# CPU.net
KiCad netlist of a schematic drawn in Altium Designer
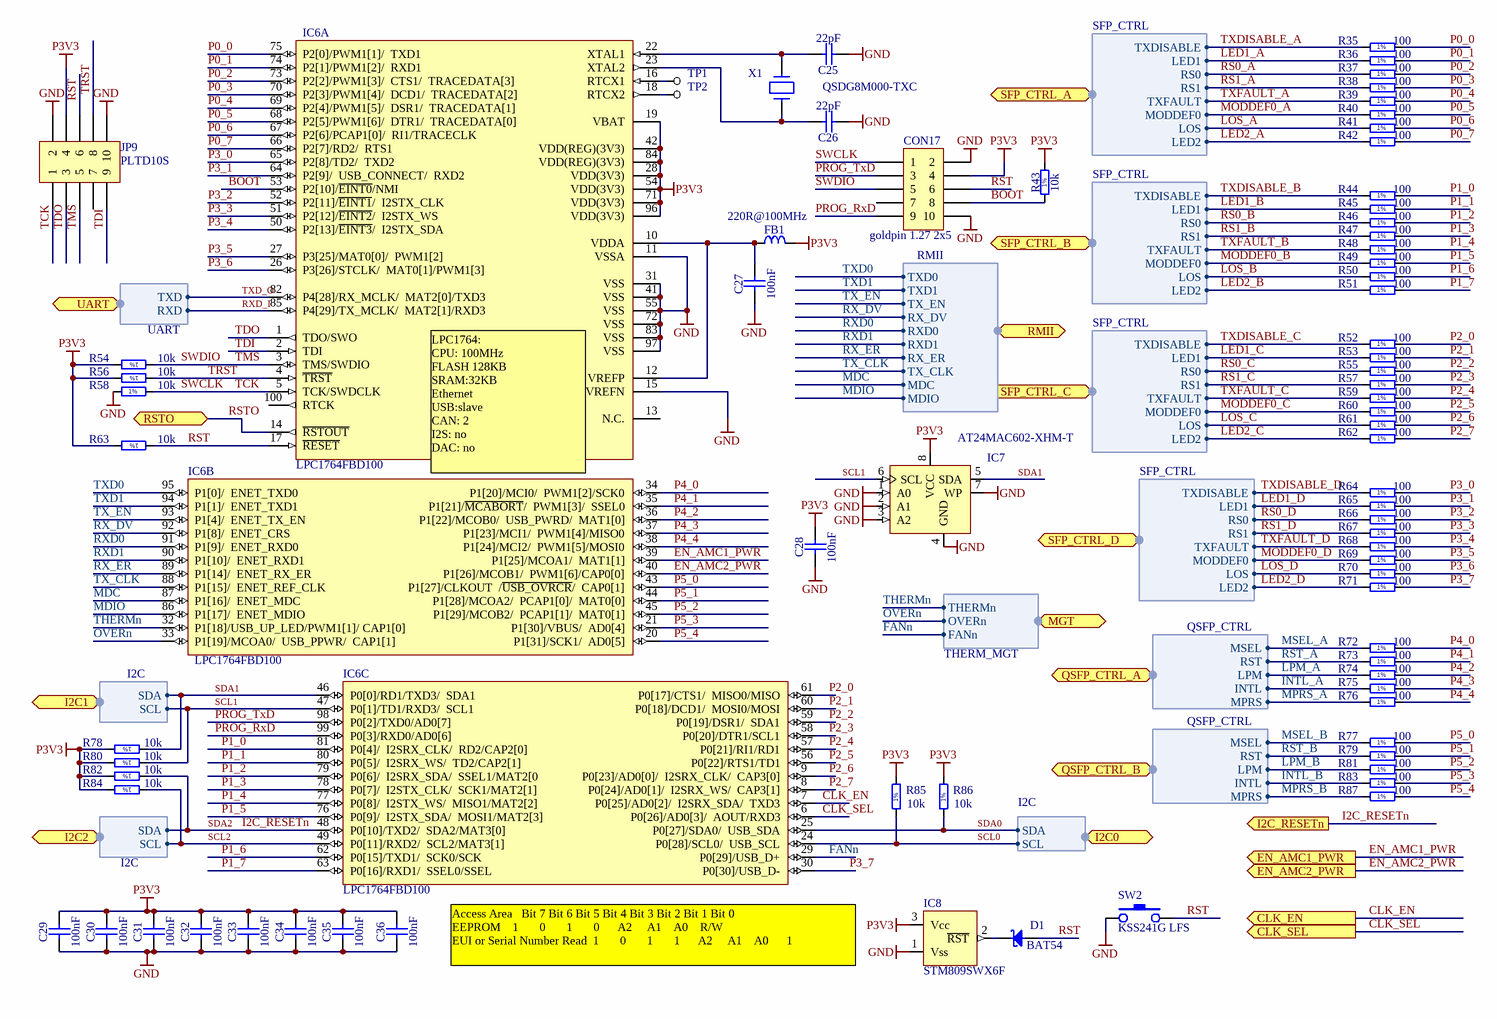
[diagram p0: CPU.SchDoc]

(export (version "E")
  (design (tool "Eeschema 10.0.6"))
  (components
    (comp (ref "C25")
      (value "22pF")
      (footprint "CAPC1005X55N")
      (description "Non-polarised capacitor")
      (fields
        (field (name "PART NUMBER") "CC0402_22PF_50V_5%_NP0")
        (field (name "VOLTAGE") "50V")
        (field (name "AUTHOR") "CERN DEM JLC")
      )
      (libsource (lib "Capacitors") (part "Capacitor - non polarized"))
    )
    (comp (ref "C26")
      (value "22pF")
      (footprint "CAPC1005X55N")
      (description "Non-polarised capacitor")
      (fields
        (field (name "PART NUMBER") "CC0402_22PF_50V_5%_NP0")
        (field (name "VOLTAGE") "50V")
        (field (name "AUTHOR") "CERN DEM JLC")
      )
      (libsource (lib "Capacitors") (part "Capacitor - non polarized"))
    )
    (comp (ref "C27")
      (value "100nF")
      (footprint "CAPC0603X33N")
      (description "Non-polarised capacitor")
      (fields
        (field (name "PART NUMBER") "CC0201_100NF_6.3V_10%_X5R")
        (field (name "VOLTAGE") "6.3V")
        (field (name "AUTHOR") "CERN DEM JLC")
      )
      (libsource (lib "Capacitors") (part "Capacitor - non polarized"))
    )
    (comp (ref "C28")
      (value "100nF")
      (footprint "CAPC0603X33N")
      (description "Non-polarised capacitor")
      (fields
        (field (name "PART NUMBER") "CC0201_100NF_6.3V_10%_X5R")
        (field (name "VOLTAGE") "6.3V")
        (field (name "AUTHOR") "CERN DEM JLC")
      )
      (libsource (lib "Capacitors") (part "Capacitor - non polarized"))
    )
    (comp (ref "C29")
      (value "100nF")
      (footprint "CAPC0603X33N")
      (description "Non-polarised capacitor")
      (fields
        (field (name "PART NUMBER") "CC0201_100NF_6.3V_10%_X5R")
        (field (name "VOLTAGE") "6.3V")
        (field (name "AUTHOR") "CERN DEM JLC")
      )
      (libsource (lib "Capacitors") (part "Capacitor - non polarized"))
    )
    (comp (ref "C30")
      (value "100nF")
      (footprint "CAPC0603X33N")
      (description "Non-polarised capacitor")
      (fields
        (field (name "PART NUMBER") "CC0201_100NF_6.3V_10%_X5R")
        (field (name "VOLTAGE") "6.3V")
        (field (name "AUTHOR") "CERN DEM JLC")
      )
      (libsource (lib "Capacitors") (part "Capacitor - non polarized"))
    )
    (comp (ref "C31")
      (value "100nF")
      (footprint "CAPC0603X33N")
      (description "Non-polarised capacitor")
      (fields
        (field (name "PART NUMBER") "CC0201_100NF_6.3V_10%_X5R")
        (field (name "VOLTAGE") "6.3V")
        (field (name "AUTHOR") "CERN DEM JLC")
      )
      (libsource (lib "Capacitors") (part "Capacitor - non polarized"))
    )
    (comp (ref "C32")
      (value "100nF")
      (footprint "CAPC0603X33N")
      (description "Non-polarised capacitor")
      (fields
        (field (name "PART NUMBER") "CC0201_100NF_6.3V_10%_X5R")
        (field (name "VOLTAGE") "6.3V")
        (field (name "AUTHOR") "CERN DEM JLC")
      )
      (libsource (lib "Capacitors") (part "Capacitor - non polarized"))
    )
    (comp (ref "C33")
      (value "100nF")
      (footprint "CAPC0603X33N")
      (description "Non-polarised capacitor")
      (fields
        (field (name "PART NUMBER") "CC0201_100NF_6.3V_10%_X5R")
        (field (name "VOLTAGE") "6.3V")
        (field (name "AUTHOR") "CERN DEM JLC")
      )
      (libsource (lib "Capacitors") (part "Capacitor - non polarized"))
    )
    (comp (ref "C34")
      (value "100nF")
      (footprint "CAPC0603X33N")
      (description "Non-polarised capacitor")
      (fields
        (field (name "PART NUMBER") "CC0201_100NF_6.3V_10%_X5R")
        (field (name "VOLTAGE") "6.3V")
        (field (name "AUTHOR") "CERN DEM JLC")
      )
      (libsource (lib "Capacitors") (part "Capacitor - non polarized"))
    )
    (comp (ref "C35")
      (value "100nF")
      (footprint "CAPC0603X33N")
      (description "Non-polarised capacitor")
      (fields
        (field (name "PART NUMBER") "CC0201_100NF_6.3V_10%_X5R")
        (field (name "VOLTAGE") "6.3V")
        (field (name "AUTHOR") "CERN DEM JLC")
      )
      (libsource (lib "Capacitors") (part "Capacitor - non polarized"))
    )
    (comp (ref "C36")
      (value "100nF")
      (footprint "CAPC0603X33N")
      (description "Non-polarised capacitor")
      (fields
        (field (name "PART NUMBER") "CC0201_100NF_6.3V_10%_X5R")
        (field (name "VOLTAGE") "6.3V")
        (field (name "AUTHOR") "CERN DEM JLC")
      )
      (libsource (lib "Capacitors") (part "Capacitor - non polarized"))
    )
    (comp (ref "CON17")
      (value "goldpin 1.27 2x5")
      (footprint "CON_2x5_MINI")
      (description "PBTD10S")
      (libsource (lib "sch") (part "CON_HEADER 5X2"))
    )
    (comp (ref "D1")
      (value "BAT54")
      (footprint "SOT95P240X130-3N")
      (description "Diode Schottky  Anode Pin 1 Cathode Pin 3 (Pas de pin 2)")
      (fields
        (field (name "VOLTAGE") "30V")
        (field (name "POWER") "200mA")
        (field (name "AUTHOR") "CERN DEM JLC")
      )
      (libsource (lib "ICs And Semiconductors") (part "Diode Schottky A1C3"))
    )
    (comp (ref "FB1")
      (value "220R@100MHz")
      (footprint "INDC2012X105N")
      (description "Inductor")
      (fields
        (field (name "PART NUMBER") "IND0805_MURATA_BLM21PG221SN1D")
        (field (name "POWER") "2A")
        (field (name "AUTHOR") "CERN DEM JLC")
      )
      (libsource (lib "Inductors & Transformers") (part "Inductor"))
    )
    (comp (ref "IC6")
      (value "LPC1764FBD100")
      (footprint "LQFP100-LPC")
      (description "ARM Cortex-M3 procesor")
      (libsource (lib "LIBRARY_SCH") (part "UPC_LPC1764"))
    )
    (comp (ref "IC7")
      (value "AT24MAC602-XHM-T")
      (footprint "TSSOP-8")
      (description "Serial 2K EEPROM+ 48bit MAC")
      (libsource (lib "LIBRARY_SCH") (part "MEM_24MAC602"))
    )
    (comp (ref "IC8")
      (value "STM809SWX6F")
      (footprint "SOT-23")
      (description "2.93V  Reset circuit")
      (libsource (lib "LIBRARY_SCH") (part "VMON_STM809"))
    )
    (comp (ref "JP9")
      (value "PLTD10S")
      (footprint "PLTD10S")
      (description "Goldpin 2.54mm, male header")
      (libsource (lib "LIBRARY_SCH") (part "CON_2x5 2.54 male SMT"))
    )
    (comp (ref "R35")
      (value "100")
      (footprint "RESC1005X40N")
      (description "Resistor - 1%")
      (fields
        (field (name "PART NUMBER") "R0402_100R_1%_0.0625W_100PPM")
        (field (name "POWER") "0.0625W")
        (field (name "AUTHOR") "CERN DEM JLC")
      )
      (libsource (lib "Resistors") (part "Resistor - 1%"))
    )
    (comp (ref "R36")
      (value "100")
      (footprint "RESC1005X40N")
      (description "Resistor - 1%")
      (fields
        (field (name "PART NUMBER") "R0402_100R_1%_0.0625W_100PPM")
        (field (name "POWER") "0.0625W")
        (field (name "AUTHOR") "CERN DEM JLC")
      )
      (libsource (lib "Resistors") (part "Resistor - 1%"))
    )
    (comp (ref "R37")
      (value "100")
      (footprint "RESC1005X40N")
      (description "Resistor - 1%")
      (fields
        (field (name "PART NUMBER") "R0402_100R_1%_0.0625W_100PPM")
        (field (name "POWER") "0.0625W")
        (field (name "AUTHOR") "CERN DEM JLC")
      )
      (libsource (lib "Resistors") (part "Resistor - 1%"))
    )
    (comp (ref "R38")
      (value "100")
      (footprint "RESC1005X40N")
      (description "Resistor - 1%")
      (fields
        (field (name "PART NUMBER") "R0402_100R_1%_0.0625W_100PPM")
        (field (name "POWER") "0.0625W")
        (field (name "AUTHOR") "CERN DEM JLC")
      )
      (libsource (lib "Resistors") (part "Resistor - 1%"))
    )
    (comp (ref "R39")
      (value "100")
      (footprint "RESC1005X40N")
      (description "Resistor - 1%")
      (fields
        (field (name "PART NUMBER") "R0402_100R_1%_0.0625W_100PPM")
        (field (name "POWER") "0.0625W")
        (field (name "AUTHOR") "CERN DEM JLC")
      )
      (libsource (lib "Resistors") (part "Resistor - 1%"))
    )
    (comp (ref "R40")
      (value "100")
      (footprint "RESC1005X40N")
      (description "Resistor - 1%")
      (fields
        (field (name "PART NUMBER") "R0402_100R_1%_0.0625W_100PPM")
        (field (name "POWER") "0.0625W")
        (field (name "AUTHOR") "CERN DEM JLC")
      )
      (libsource (lib "Resistors") (part "Resistor - 1%"))
    )
    (comp (ref "R41")
      (value "100")
      (footprint "RESC1005X40N")
      (description "Resistor - 1%")
      (fields
        (field (name "PART NUMBER") "R0402_100R_1%_0.0625W_100PPM")
        (field (name "POWER") "0.0625W")
        (field (name "AUTHOR") "CERN DEM JLC")
      )
      (libsource (lib "Resistors") (part "Resistor - 1%"))
    )
    (comp (ref "R42")
      (value "100")
      (footprint "RESC1005X40N")
      (description "Resistor - 1%")
      (fields
        (field (name "PART NUMBER") "R0402_100R_1%_0.0625W_100PPM")
        (field (name "POWER") "0.0625W")
        (field (name "AUTHOR") "CERN DEM JLC")
      )
      (libsource (lib "Resistors") (part "Resistor - 1%"))
    )
    (comp (ref "R43")
      (value "10k")
      (footprint "RESC1005X40N")
      (description "Resistor - 1%")
      (fields
        (field (name "PART NUMBER") "R0402_10K_1%_0.0625W_100PPM")
        (field (name "POWER") "0.0625W")
        (field (name "AUTHOR") "CERN DEM JLC")
      )
      (libsource (lib "Resistors") (part "Resistor - 1%"))
    )
    (comp (ref "R44")
      (value "100")
      (footprint "RESC1005X40N")
      (description "Resistor - 1%")
      (fields
        (field (name "PART NUMBER") "R0402_100R_1%_0.0625W_100PPM")
        (field (name "POWER") "0.0625W")
        (field (name "AUTHOR") "CERN DEM JLC")
      )
      (libsource (lib "Resistors") (part "Resistor - 1%"))
    )
    (comp (ref "R45")
      (value "100")
      (footprint "RESC1005X40N")
      (description "Resistor - 1%")
      (fields
        (field (name "PART NUMBER") "R0402_100R_1%_0.0625W_100PPM")
        (field (name "POWER") "0.0625W")
        (field (name "AUTHOR") "CERN DEM JLC")
      )
      (libsource (lib "Resistors") (part "Resistor - 1%"))
    )
    (comp (ref "R46")
      (value "100")
      (footprint "RESC1005X40N")
      (description "Resistor - 1%")
      (fields
        (field (name "PART NUMBER") "R0402_100R_1%_0.0625W_100PPM")
        (field (name "POWER") "0.0625W")
        (field (name "AUTHOR") "CERN DEM JLC")
      )
      (libsource (lib "Resistors") (part "Resistor - 1%"))
    )
    (comp (ref "R47")
      (value "100")
      (footprint "RESC1005X40N")
      (description "Resistor - 1%")
      (fields
        (field (name "PART NUMBER") "R0402_100R_1%_0.0625W_100PPM")
        (field (name "POWER") "0.0625W")
        (field (name "AUTHOR") "CERN DEM JLC")
      )
      (libsource (lib "Resistors") (part "Resistor - 1%"))
    )
    (comp (ref "R48")
      (value "100")
      (footprint "RESC1005X40N")
      (description "Resistor - 1%")
      (fields
        (field (name "PART NUMBER") "R0402_100R_1%_0.0625W_100PPM")
        (field (name "POWER") "0.0625W")
        (field (name "AUTHOR") "CERN DEM JLC")
      )
      (libsource (lib "Resistors") (part "Resistor - 1%"))
    )
    (comp (ref "R49")
      (value "100")
      (footprint "RESC1005X40N")
      (description "Resistor - 1%")
      (fields
        (field (name "PART NUMBER") "R0402_100R_1%_0.0625W_100PPM")
        (field (name "POWER") "0.0625W")
        (field (name "AUTHOR") "CERN DEM JLC")
      )
      (libsource (lib "Resistors") (part "Resistor - 1%"))
    )
    (comp (ref "R50")
      (value "100")
      (footprint "RESC1005X40N")
      (description "Resistor - 1%")
      (fields
        (field (name "PART NUMBER") "R0402_100R_1%_0.0625W_100PPM")
        (field (name "POWER") "0.0625W")
        (field (name "AUTHOR") "CERN DEM JLC")
      )
      (libsource (lib "Resistors") (part "Resistor - 1%"))
    )
    (comp (ref "R51")
      (value "100")
      (footprint "RESC1005X40N")
      (description "Resistor - 1%")
      (fields
        (field (name "PART NUMBER") "R0402_100R_1%_0.0625W_100PPM")
        (field (name "POWER") "0.0625W")
        (field (name "AUTHOR") "CERN DEM JLC")
      )
      (libsource (lib "Resistors") (part "Resistor - 1%"))
    )
    (comp (ref "R52")
      (value "100")
      (footprint "RESC1005X40N")
      (description "Resistor - 1%")
      (fields
        (field (name "PART NUMBER") "R0402_100R_1%_0.0625W_100PPM")
        (field (name "POWER") "0.0625W")
        (field (name "AUTHOR") "CERN DEM JLC")
      )
      (libsource (lib "Resistors") (part "Resistor - 1%"))
    )
    (comp (ref "R53")
      (value "100")
      (footprint "RESC1005X40N")
      (description "Resistor - 1%")
      (fields
        (field (name "PART NUMBER") "R0402_100R_1%_0.0625W_100PPM")
        (field (name "POWER") "0.0625W")
        (field (name "AUTHOR") "CERN DEM JLC")
      )
      (libsource (lib "Resistors") (part "Resistor - 1%"))
    )
    (comp (ref "R54")
      (value "10k")
      (footprint "RESC1005X40N")
      (description "Resistor - 1%")
      (fields
        (field (name "PART NUMBER") "R0402_10K_1%_0.0625W_100PPM")
        (field (name "POWER") "0.0625W")
        (field (name "AUTHOR") "CERN DEM JLC")
      )
      (libsource (lib "Resistors") (part "Resistor - 1%"))
    )
    (comp (ref "R55")
      (value "100")
      (footprint "RESC1005X40N")
      (description "Resistor - 1%")
      (fields
        (field (name "PART NUMBER") "R0402_100R_1%_0.0625W_100PPM")
        (field (name "POWER") "0.0625W")
        (field (name "AUTHOR") "CERN DEM JLC")
      )
      (libsource (lib "Resistors") (part "Resistor - 1%"))
    )
    (comp (ref "R56")
      (value "10k")
      (footprint "RESC1005X40N")
      (description "Resistor - 1%")
      (fields
        (field (name "PART NUMBER") "R0402_10K_1%_0.0625W_100PPM")
        (field (name "POWER") "0.0625W")
        (field (name "AUTHOR") "CERN DEM JLC")
      )
      (libsource (lib "Resistors") (part "Resistor - 1%"))
    )
    (comp (ref "R57")
      (value "100")
      (footprint "RESC1005X40N")
      (description "Resistor - 1%")
      (fields
        (field (name "PART NUMBER") "R0402_100R_1%_0.0625W_100PPM")
        (field (name "POWER") "0.0625W")
        (field (name "AUTHOR") "CERN DEM JLC")
      )
      (libsource (lib "Resistors") (part "Resistor - 1%"))
    )
    (comp (ref "R58")
      (value "10k")
      (footprint "RESC1005X40N")
      (description "Resistor - 1%")
      (fields
        (field (name "PART NUMBER") "R0402_10K_1%_0.0625W_100PPM")
        (field (name "POWER") "0.0625W")
        (field (name "AUTHOR") "CERN DEM JLC")
      )
      (libsource (lib "Resistors") (part "Resistor - 1%"))
    )
    (comp (ref "R59")
      (value "100")
      (footprint "RESC1005X40N")
      (description "Resistor - 1%")
      (fields
        (field (name "PART NUMBER") "R0402_100R_1%_0.0625W_100PPM")
        (field (name "POWER") "0.0625W")
        (field (name "AUTHOR") "CERN DEM JLC")
      )
      (libsource (lib "Resistors") (part "Resistor - 1%"))
    )
    (comp (ref "R60")
      (value "100")
      (footprint "RESC1005X40N")
      (description "Resistor - 1%")
      (fields
        (field (name "PART NUMBER") "R0402_100R_1%_0.0625W_100PPM")
        (field (name "POWER") "0.0625W")
        (field (name "AUTHOR") "CERN DEM JLC")
      )
      (libsource (lib "Resistors") (part "Resistor - 1%"))
    )
    (comp (ref "R61")
      (value "100")
      (footprint "RESC1005X40N")
      (description "Resistor - 1%")
      (fields
        (field (name "PART NUMBER") "R0402_100R_1%_0.0625W_100PPM")
        (field (name "POWER") "0.0625W")
        (field (name "AUTHOR") "CERN DEM JLC")
      )
      (libsource (lib "Resistors") (part "Resistor - 1%"))
    )
    (comp (ref "R62")
      (value "100")
      (footprint "RESC1005X40N")
      (description "Resistor - 1%")
      (fields
        (field (name "PART NUMBER") "R0402_100R_1%_0.0625W_100PPM")
        (field (name "POWER") "0.0625W")
        (field (name "AUTHOR") "CERN DEM JLC")
      )
      (libsource (lib "Resistors") (part "Resistor - 1%"))
    )
    (comp (ref "R63")
      (value "10k")
      (footprint "RESC1005X40N")
      (description "Resistor - 1%")
      (fields
        (field (name "PART NUMBER") "R0402_10K_1%_0.0625W_100PPM")
        (field (name "POWER") "0.0625W")
        (field (name "AUTHOR") "CERN DEM JLC")
      )
      (libsource (lib "Resistors") (part "Resistor - 1%"))
    )
    (comp (ref "R64")
      (value "100")
      (footprint "RESC1005X40N")
      (description "Resistor - 1%")
      (fields
        (field (name "PART NUMBER") "R0402_100R_1%_0.0625W_100PPM")
        (field (name "POWER") "0.0625W")
        (field (name "AUTHOR") "CERN DEM JLC")
      )
      (libsource (lib "Resistors") (part "Resistor - 1%"))
    )
    (comp (ref "R65")
      (value "100")
      (footprint "RESC1005X40N")
      (description "Resistor - 1%")
      (fields
        (field (name "PART NUMBER") "R0402_100R_1%_0.0625W_100PPM")
        (field (name "POWER") "0.0625W")
        (field (name "AUTHOR") "CERN DEM JLC")
      )
      (libsource (lib "Resistors") (part "Resistor - 1%"))
    )
    (comp (ref "R66")
      (value "100")
      (footprint "RESC1005X40N")
      (description "Resistor - 1%")
      (fields
        (field (name "PART NUMBER") "R0402_100R_1%_0.0625W_100PPM")
        (field (name "POWER") "0.0625W")
        (field (name "AUTHOR") "CERN DEM JLC")
      )
      (libsource (lib "Resistors") (part "Resistor - 1%"))
    )
    (comp (ref "R67")
      (value "100")
      (footprint "RESC1005X40N")
      (description "Resistor - 1%")
      (fields
        (field (name "PART NUMBER") "R0402_100R_1%_0.0625W_100PPM")
        (field (name "POWER") "0.0625W")
        (field (name "AUTHOR") "CERN DEM JLC")
      )
      (libsource (lib "Resistors") (part "Resistor - 1%"))
    )
    (comp (ref "R68")
      (value "100")
      (footprint "RESC1005X40N")
      (description "Resistor - 1%")
      (fields
        (field (name "PART NUMBER") "R0402_100R_1%_0.0625W_100PPM")
        (field (name "POWER") "0.0625W")
        (field (name "AUTHOR") "CERN DEM JLC")
      )
      (libsource (lib "Resistors") (part "Resistor - 1%"))
    )
    (comp (ref "R69")
      (value "100")
      (footprint "RESC1005X40N")
      (description "Resistor - 1%")
      (fields
        (field (name "PART NUMBER") "R0402_100R_1%_0.0625W_100PPM")
        (field (name "POWER") "0.0625W")
        (field (name "AUTHOR") "CERN DEM JLC")
      )
      (libsource (lib "Resistors") (part "Resistor - 1%"))
    )
    (comp (ref "R70")
      (value "100")
      (footprint "RESC1005X40N")
      (description "Resistor - 1%")
      (fields
        (field (name "PART NUMBER") "R0402_100R_1%_0.0625W_100PPM")
        (field (name "POWER") "0.0625W")
        (field (name "AUTHOR") "CERN DEM JLC")
      )
      (libsource (lib "Resistors") (part "Resistor - 1%"))
    )
    (comp (ref "R71")
      (value "100")
      (footprint "RESC1005X40N")
      (description "Resistor - 1%")
      (fields
        (field (name "PART NUMBER") "R0402_100R_1%_0.0625W_100PPM")
        (field (name "POWER") "0.0625W")
        (field (name "AUTHOR") "CERN DEM JLC")
      )
      (libsource (lib "Resistors") (part "Resistor - 1%"))
    )
    (comp (ref "R72")
      (value "100")
      (footprint "RESC1005X40N")
      (description "Resistor - 1%")
      (fields
        (field (name "PART NUMBER") "R0402_100R_1%_0.0625W_100PPM")
        (field (name "POWER") "0.0625W")
        (field (name "AUTHOR") "CERN DEM JLC")
      )
      (libsource (lib "Resistors") (part "Resistor - 1%"))
    )
    (comp (ref "R73")
      (value "100")
      (footprint "RESC1005X40N")
      (description "Resistor - 1%")
      (fields
        (field (name "PART NUMBER") "R0402_100R_1%_0.0625W_100PPM")
        (field (name "POWER") "0.0625W")
        (field (name "AUTHOR") "CERN DEM JLC")
      )
      (libsource (lib "Resistors") (part "Resistor - 1%"))
    )
    (comp (ref "R74")
      (value "100")
      (footprint "RESC1005X40N")
      (description "Resistor - 1%")
      (fields
        (field (name "PART NUMBER") "R0402_100R_1%_0.0625W_100PPM")
        (field (name "POWER") "0.0625W")
        (field (name "AUTHOR") "CERN DEM JLC")
      )
      (libsource (lib "Resistors") (part "Resistor - 1%"))
    )
    (comp (ref "R75")
      (value "100")
      (footprint "RESC1005X40N")
      (description "Resistor - 1%")
      (fields
        (field (name "PART NUMBER") "R0402_100R_1%_0.0625W_100PPM")
        (field (name "POWER") "0.0625W")
        (field (name "AUTHOR") "CERN DEM JLC")
      )
      (libsource (lib "Resistors") (part "Resistor - 1%"))
    )
    (comp (ref "R76")
      (value "100")
      (footprint "RESC1005X40N")
      (description "Resistor - 1%")
      (fields
        (field (name "PART NUMBER") "R0402_100R_1%_0.0625W_100PPM")
        (field (name "POWER") "0.0625W")
        (field (name "AUTHOR") "CERN DEM JLC")
      )
      (libsource (lib "Resistors") (part "Resistor - 1%"))
    )
    (comp (ref "R77")
      (value "100")
      (footprint "RESC1005X40N")
      (description "Resistor - 1%")
      (fields
        (field (name "PART NUMBER") "R0402_100R_1%_0.0625W_100PPM")
        (field (name "POWER") "0.0625W")
        (field (name "AUTHOR") "CERN DEM JLC")
      )
      (libsource (lib "Resistors") (part "Resistor - 1%"))
    )
    (comp (ref "R78")
      (value "10k")
      (footprint "RESC1005X40N")
      (description "Resistor - 1%")
      (fields
        (field (name "PART NUMBER") "R0402_10K_1%_0.0625W_100PPM")
        (field (name "POWER") "0.0625W")
        (field (name "AUTHOR") "CERN DEM JLC")
      )
      (libsource (lib "Resistors") (part "Resistor - 1%"))
    )
    (comp (ref "R79")
      (value "100")
      (footprint "RESC1005X40N")
      (description "Resistor - 1%")
      (fields
        (field (name "PART NUMBER") "R0402_100R_1%_0.0625W_100PPM")
        (field (name "POWER") "0.0625W")
        (field (name "AUTHOR") "CERN DEM JLC")
      )
      (libsource (lib "Resistors") (part "Resistor - 1%"))
    )
    (comp (ref "R80")
      (value "10k")
      (footprint "RESC1005X40N")
      (description "Resistor - 1%")
      (fields
        (field (name "PART NUMBER") "R0402_10K_1%_0.0625W_100PPM")
        (field (name "POWER") "0.0625W")
        (field (name "AUTHOR") "CERN DEM JLC")
      )
      (libsource (lib "Resistors") (part "Resistor - 1%"))
    )
    (comp (ref "R81")
      (value "100")
      (footprint "RESC1005X40N")
      (description "Resistor - 1%")
      (fields
        (field (name "PART NUMBER") "R0402_100R_1%_0.0625W_100PPM")
        (field (name "POWER") "0.0625W")
        (field (name "AUTHOR") "CERN DEM JLC")
      )
      (libsource (lib "Resistors") (part "Resistor - 1%"))
    )
    (comp (ref "R82")
      (value "10k")
      (footprint "RESC1005X40N")
      (description "Resistor - 1%")
      (fields
        (field (name "PART NUMBER") "R0402_10K_1%_0.0625W_100PPM")
        (field (name "POWER") "0.0625W")
        (field (name "AUTHOR") "CERN DEM JLC")
      )
      (libsource (lib "Resistors") (part "Resistor - 1%"))
    )
    (comp (ref "R83")
      (value "100")
      (footprint "RESC1005X40N")
      (description "Resistor - 1%")
      (fields
        (field (name "PART NUMBER") "R0402_100R_1%_0.0625W_100PPM")
        (field (name "POWER") "0.0625W")
        (field (name "AUTHOR") "CERN DEM JLC")
      )
      (libsource (lib "Resistors") (part "Resistor - 1%"))
    )
    (comp (ref "R84")
      (value "10k")
      (footprint "RESC1005X40N")
      (description "Resistor - 1%")
      (fields
        (field (name "PART NUMBER") "R0402_10K_1%_0.0625W_100PPM")
        (field (name "POWER") "0.0625W")
        (field (name "AUTHOR") "CERN DEM JLC")
      )
      (libsource (lib "Resistors") (part "Resistor - 1%"))
    )
    (comp (ref "R85")
      (value "10k")
      (footprint "RESC1005X40N")
      (description "Resistor - 1%")
      (fields
        (field (name "PART NUMBER") "R0402_10K_1%_0.0625W_100PPM")
        (field (name "POWER") "0.0625W")
        (field (name "AUTHOR") "CERN DEM JLC")
      )
      (libsource (lib "Resistors") (part "Resistor - 1%"))
    )
    (comp (ref "R86")
      (value "10k")
      (footprint "RESC1005X40N")
      (description "Resistor - 1%")
      (fields
        (field (name "PART NUMBER") "R0402_10K_1%_0.0625W_100PPM")
        (field (name "POWER") "0.0625W")
        (field (name "AUTHOR") "CERN DEM JLC")
      )
      (libsource (lib "Resistors") (part "Resistor - 1%"))
    )
    (comp (ref "R87")
      (value "100")
      (footprint "RESC1005X40N")
      (description "Resistor - 1%")
      (fields
        (field (name "PART NUMBER") "R0402_100R_1%_0.0625W_100PPM")
        (field (name "POWER") "0.0625W")
        (field (name "AUTHOR") "CERN DEM JLC")
      )
      (libsource (lib "Resistors") (part "Resistor - 1%"))
    )
    (comp (ref "SW2")
      (value "KSS241G LFS")
      (footprint "KSS241G LFS")
      (description "Push button")
      (libsource (lib "LIBRARY_SCH") (part "SW-TACT_SMD_RA_mini"))
    )
    (comp (ref "TP1")
      (value "TP")
      (footprint "TP")
      (description "Testpoint")
      (libsource (lib "LIBRARY_SCH") (part "TP"))
    )
    (comp (ref "TP2")
      (value "TP")
      (footprint "TP")
      (description "Testpoint")
      (libsource (lib "LIBRARY_SCH") (part "TP"))
    )
    (comp (ref "X1")
      (value "QSDG8M000-TXC")
      (footprint "XTAL_5.0*3.2")
      (description "miniature crystal oscillator (Maritex) QSDG8M000-TXC")
      (libsource (lib "LIBRARY_SCH") (part "X_CRYSTAL_SMD_5.0*3.2"))
    )
  )
  (nets
    (net (code "7") (name "/BOOT") (class "Default")
      (node (ref "CON17") (pin "8") (pinfunction "8_8") (pintype "passive"))
      (node (ref "IC6") (pin "53") (pinfunction "P2[10]/~{EINT0}/NMI_53") (pintype "bidirectional"))
      (node (ref "R43") (pin "1") (pinfunction "1_1") (pintype "passive"))
    )
    (net (code "8") (name "/CLK_EN") (class "Default")
      (node (ref "IC6") (pin "7") (pinfunction "P0[25]/AD0[2]/__I2SRX_SDA/__TXD3_7") (pintype "bidirectional"))
    )
    (net (code "9") (name "/CLK_SEL") (class "Default")
      (node (ref "IC6") (pin "6") (pinfunction "P0[26]/AD0[3]/__AOUT/RXD3_6") (pintype "bidirectional"))
    )
    (net (code "10") (name "/EN_AMC1_PWR") (class "Default")
      (node (ref "IC6") (pin "39") (pinfunction "P1[25]/MCOA1/__MAT1[1]_39") (pintype "bidirectional"))
    )
    (net (code "11") (name "/EN_AMC2_PWR") (class "Default")
      (node (ref "IC6") (pin "40") (pinfunction "P1[26]/MCOB1/__PWM1[6]/CAP0[0]_40") (pintype "bidirectional"))
    )
    (net (code "12") (name "/FANn") (class "Default")
      (node (ref "IC6") (pin "29") (pinfunction "P0[29]/USB_D+_29") (pintype "bidirectional"))
    )
    (net (code "13") (name "/I2C_RESETn") (class "Default")
      (node (ref "IC6") (pin "48") (pinfunction "P0[10]/TXD2/__SDA2/MAT3[0]_48") (pintype "bidirectional"))
      (node (ref "R82") (pin "1") (pinfunction "1_1") (pintype "passive"))
    )
    (net (code "14") (name "/INTL_A") (class "Default")
      (node (ref "R75") (pin "1") (pinfunction "1_1") (pintype "passive"))
    )
    (net (code "15") (name "/INTL_B") (class "Default")
      (node (ref "R83") (pin "1") (pinfunction "1_1") (pintype "passive"))
    )
    (net (code "16") (name "/LED1_A") (class "Default")
      (node (ref "R36") (pin "1") (pinfunction "1_1") (pintype "passive"))
    )
    (net (code "17") (name "/LED1_B") (class "Default")
      (node (ref "R45") (pin "1") (pinfunction "1_1") (pintype "passive"))
    )
    (net (code "18") (name "/LED1_C") (class "Default")
      (node (ref "R53") (pin "1") (pinfunction "1_1") (pintype "passive"))
    )
    (net (code "19") (name "/LED1_D") (class "Default")
      (node (ref "R65") (pin "1") (pinfunction "1_1") (pintype "passive"))
    )
    (net (code "20") (name "/LED2_A") (class "Default")
      (node (ref "R42") (pin "1") (pinfunction "1_1") (pintype "passive"))
    )
    (net (code "21") (name "/LED2_B") (class "Default")
      (node (ref "R51") (pin "1") (pinfunction "1_1") (pintype "passive"))
    )
    (net (code "22") (name "/LED2_C") (class "Default")
      (node (ref "R62") (pin "1") (pinfunction "1_1") (pintype "passive"))
    )
    (net (code "23") (name "/LED2_D") (class "Default")
      (node (ref "R71") (pin "1") (pinfunction "1_1") (pintype "passive"))
    )
    (net (code "24") (name "/LOS_A") (class "Default")
      (node (ref "R41") (pin "1") (pinfunction "1_1") (pintype "passive"))
    )
    (net (code "25") (name "/LOS_B") (class "Default")
      (node (ref "R50") (pin "1") (pinfunction "1_1") (pintype "passive"))
    )
    (net (code "26") (name "/LOS_C") (class "Default")
      (node (ref "R61") (pin "1") (pinfunction "1_1") (pintype "passive"))
    )
    (net (code "27") (name "/LOS_D") (class "Default")
      (node (ref "R70") (pin "1") (pinfunction "1_1") (pintype "passive"))
    )
    (net (code "28") (name "/LPM_A") (class "Default")
      (node (ref "R74") (pin "1") (pinfunction "1_1") (pintype "passive"))
    )
    (net (code "29") (name "/LPM_B") (class "Default")
      (node (ref "R81") (pin "1") (pinfunction "1_1") (pintype "passive"))
    )
    (net (code "30") (name "/MDC") (class "Default")
      (node (ref "IC6") (pin "87") (pinfunction "P1[16]/__ENET_MDC_87") (pintype "bidirectional"))
    )
    (net (code "31") (name "/MDIO") (class "Default")
      (node (ref "IC6") (pin "86") (pinfunction "P1[17]/__ENET_MDIO_86") (pintype "bidirectional"))
    )
    (net (code "32") (name "/MODDEF0_A") (class "Default")
      (node (ref "R40") (pin "1") (pinfunction "1_1") (pintype "passive"))
    )
    (net (code "33") (name "/MODDEF0_B") (class "Default")
      (node (ref "R49") (pin "1") (pinfunction "1_1") (pintype "passive"))
    )
    (net (code "34") (name "/MODDEF0_C") (class "Default")
      (node (ref "R60") (pin "1") (pinfunction "1_1") (pintype "passive"))
    )
    (net (code "35") (name "/MODDEF0_D") (class "Default")
      (node (ref "R69") (pin "1") (pinfunction "1_1") (pintype "passive"))
    )
    (net (code "36") (name "/MPRS_A") (class "Default")
      (node (ref "R76") (pin "1") (pinfunction "1_1") (pintype "passive"))
    )
    (net (code "37") (name "/MPRS_B") (class "Default")
      (node (ref "R87") (pin "1") (pinfunction "1_1") (pintype "passive"))
    )
    (net (code "38") (name "/MSEL_A") (class "Default")
      (node (ref "R72") (pin "1") (pinfunction "1_1") (pintype "passive"))
    )
    (net (code "39") (name "/MSEL_B") (class "Default")
      (node (ref "R77") (pin "1") (pinfunction "1_1") (pintype "passive"))
    )
    (net (code "40") (name "/OVERn") (class "Default")
      (node (ref "IC6") (pin "33") (pinfunction "P1[19]/MCOA0/__USB_PPWR/__CAP1[1]_33") (pintype "bidirectional"))
    )
    (net (code "41") (name "/P0_0") (class "Default")
      (node (ref "IC6") (pin "75") (pinfunction "P2[0]/PWM1[1]/__TXD1_75") (pintype "bidirectional"))
      (node (ref "R35") (pin "2") (pinfunction "2_2") (pintype "passive"))
    )
    (net (code "42") (name "/P0_1") (class "Default")
      (node (ref "IC6") (pin "74") (pinfunction "P2[1]/PWM1[2]/__RXD1_74") (pintype "bidirectional"))
      (node (ref "R36") (pin "2") (pinfunction "2_2") (pintype "passive"))
    )
    (net (code "43") (name "/P0_2") (class "Default")
      (node (ref "IC6") (pin "73") (pinfunction "P2[2]/PWM1[3]/__CTS1/__TRACEDATA[3]_73") (pintype "bidirectional"))
      (node (ref "R37") (pin "2") (pinfunction "2_2") (pintype "passive"))
    )
    (net (code "44") (name "/P0_3") (class "Default")
      (node (ref "IC6") (pin "70") (pinfunction "P2[3]/PWM1[4]/__DCD1/__TRACEDATA[2]_70") (pintype "bidirectional"))
      (node (ref "R38") (pin "2") (pinfunction "2_2") (pintype "passive"))
    )
    (net (code "45") (name "/P0_4") (class "Default")
      (node (ref "IC6") (pin "69") (pinfunction "P2[4]/PWM1[5]/__DSR1/__TRACEDATA[1]_69") (pintype "bidirectional"))
      (node (ref "R39") (pin "2") (pinfunction "2_2") (pintype "passive"))
    )
    (net (code "46") (name "/P0_5") (class "Default")
      (node (ref "IC6") (pin "68") (pinfunction "P2[5]/PWM1[6]/__DTR1/__TRACEDATA[0]_68") (pintype "bidirectional"))
      (node (ref "R40") (pin "2") (pinfunction "2_2") (pintype "passive"))
    )
    (net (code "47") (name "/P0_6") (class "Default")
      (node (ref "IC6") (pin "67") (pinfunction "P2[6]/PCAP1[0]/__RI1/TRACECLK_67") (pintype "bidirectional"))
      (node (ref "R41") (pin "2") (pinfunction "2_2") (pintype "passive"))
    )
    (net (code "48") (name "/P0_7") (class "Default")
      (node (ref "IC6") (pin "66") (pinfunction "P2[7]/RD2/__RTS1_66") (pintype "bidirectional"))
      (node (ref "R42") (pin "2") (pinfunction "2_2") (pintype "passive"))
    )
    (net (code "49") (name "/P1_0") (class "Default")
      (node (ref "IC6") (pin "81") (pinfunction "P0[4]/__I2SRX_CLK/__RD2/CAP2[0]_81") (pintype "bidirectional"))
      (node (ref "R44") (pin "2") (pinfunction "2_2") (pintype "passive"))
    )
    (net (code "50") (name "/P1_1") (class "Default")
      (node (ref "IC6") (pin "80") (pinfunction "P0[5]/__I2SRX_WS/__TD2/CAP2[1]_80") (pintype "bidirectional"))
      (node (ref "R45") (pin "2") (pinfunction "2_2") (pintype "passive"))
    )
    (net (code "51") (name "/P1_2") (class "Default")
      (node (ref "IC6") (pin "79") (pinfunction "P0[6]/__I2SRX_SDA/__SSEL1/MAT2[0_79") (pintype "bidirectional"))
      (node (ref "R46") (pin "2") (pinfunction "2_2") (pintype "passive"))
    )
    (net (code "52") (name "/P1_3") (class "Default")
      (node (ref "IC6") (pin "78") (pinfunction "P0[7]/__I2STX_CLK/__SCK1/MAT2[1]_78") (pintype "bidirectional"))
      (node (ref "R47") (pin "2") (pinfunction "2_2") (pintype "passive"))
    )
    (net (code "53") (name "/P1_4") (class "Default")
      (node (ref "IC6") (pin "77") (pinfunction "P0[8]/__I2STX_WS/__MISO1/MAT2[2]_77") (pintype "bidirectional"))
      (node (ref "R48") (pin "2") (pinfunction "2_2") (pintype "passive"))
    )
    (net (code "54") (name "/P1_5") (class "Default")
      (node (ref "IC6") (pin "76") (pinfunction "P0[9]/__I2STX_SDA/__MOSI1/MAT2[3]_76") (pintype "bidirectional"))
      (node (ref "R49") (pin "2") (pinfunction "2_2") (pintype "passive"))
    )
    (net (code "55") (name "/P1_6") (class "Default")
      (node (ref "IC6") (pin "62") (pinfunction "P0[15]/TXD1/__SCK0/SCK_62") (pintype "bidirectional"))
      (node (ref "R50") (pin "2") (pinfunction "2_2") (pintype "passive"))
    )
    (net (code "56") (name "/P1_7") (class "Default")
      (node (ref "IC6") (pin "63") (pinfunction "P0[16]/RXD1/__SSEL0/SSEL_63") (pintype "bidirectional"))
      (node (ref "R51") (pin "2") (pinfunction "2_2") (pintype "passive"))
    )
    (net (code "57") (name "/P2_0") (class "Default")
      (node (ref "IC6") (pin "61") (pinfunction "P0[17]/CTS1/__MISO0/MISO_61") (pintype "bidirectional"))
      (node (ref "R52") (pin "2") (pinfunction "2_2") (pintype "passive"))
    )
    (net (code "58") (name "/P2_1") (class "Default")
      (node (ref "IC6") (pin "60") (pinfunction "P0[18]/DCD1/__MOSI0/MOSI_60") (pintype "bidirectional"))
      (node (ref "R53") (pin "2") (pinfunction "2_2") (pintype "passive"))
    )
    (net (code "59") (name "/P2_2") (class "Default")
      (node (ref "IC6") (pin "59") (pinfunction "P0[19]/DSR1/__SDA1_59") (pintype "bidirectional"))
      (node (ref "R55") (pin "2") (pinfunction "2_2") (pintype "passive"))
    )
    (net (code "60") (name "/P2_3") (class "Default")
      (node (ref "IC6") (pin "58") (pinfunction "P0[20]/DTR1/SCL1_58") (pintype "bidirectional"))
      (node (ref "R57") (pin "2") (pinfunction "2_2") (pintype "passive"))
    )
    (net (code "61") (name "/P2_4") (class "Default")
      (node (ref "IC6") (pin "57") (pinfunction "P0[21]/RI1/RD1_57") (pintype "bidirectional"))
      (node (ref "R59") (pin "2") (pinfunction "2_2") (pintype "passive"))
    )
    (net (code "62") (name "/P2_5") (class "Default")
      (node (ref "IC6") (pin "56") (pinfunction "P0[22]/RTS1/TD1_56") (pintype "bidirectional"))
      (node (ref "R60") (pin "2") (pinfunction "2_2") (pintype "passive"))
    )
    (net (code "63") (name "/P2_6") (class "Default")
      (node (ref "IC6") (pin "9") (pinfunction "P0[23]/AD0[0]/__I2SRX_CLK/__CAP3[0]_9") (pintype "bidirectional"))
      (node (ref "R61") (pin "2") (pinfunction "2_2") (pintype "passive"))
    )
    (net (code "64") (name "/P2_7") (class "Default")
      (node (ref "IC6") (pin "8") (pinfunction "P0[24]/AD0[1]/__I2SRX_WS/__CAP3[1]_8") (pintype "bidirectional"))
      (node (ref "R62") (pin "2") (pinfunction "2_2") (pintype "passive"))
    )
    (net (code "65") (name "/P3_0") (class "Default")
      (node (ref "IC6") (pin "65") (pinfunction "P2[8]/TD2/__TXD2_65") (pintype "bidirectional"))
      (node (ref "R64") (pin "2") (pinfunction "2_2") (pintype "passive"))
    )
    (net (code "66") (name "/P3_1") (class "Default")
      (node (ref "IC6") (pin "64") (pinfunction "P2[9]/__USB_CONNECT/__RXD2_64") (pintype "bidirectional"))
      (node (ref "R65") (pin "2") (pinfunction "2_2") (pintype "passive"))
    )
    (net (code "67") (name "/P3_2") (class "Default")
      (node (ref "IC6") (pin "52") (pinfunction "P2[11]/~{EINT1}/__I2STX_CLK_52") (pintype "bidirectional"))
      (node (ref "R66") (pin "2") (pinfunction "2_2") (pintype "passive"))
    )
    (net (code "68") (name "/P3_3") (class "Default")
      (node (ref "IC6") (pin "51") (pinfunction "P2[12]/~{EINT2}/__I2STX_WS_51") (pintype "bidirectional"))
      (node (ref "R67") (pin "2") (pinfunction "2_2") (pintype "passive"))
    )
    (net (code "69") (name "/P3_4") (class "Default")
      (node (ref "IC6") (pin "50") (pinfunction "P2[13]/~{EINT3}/__I2STX_SDA_50") (pintype "bidirectional"))
      (node (ref "R68") (pin "2") (pinfunction "2_2") (pintype "passive"))
    )
    (net (code "70") (name "/P3_5") (class "Default")
      (node (ref "IC6") (pin "27") (pinfunction "P3[25]/MAT0[0]/__PWM1[2]_27") (pintype "bidirectional"))
      (node (ref "R69") (pin "2") (pinfunction "2_2") (pintype "passive"))
    )
    (net (code "71") (name "/P3_6") (class "Default")
      (node (ref "IC6") (pin "26") (pinfunction "P3[26]/STCLK/__MAT0[1]/PWM1[3]_26") (pintype "bidirectional"))
      (node (ref "R70") (pin "2") (pinfunction "2_2") (pintype "passive"))
    )
    (net (code "72") (name "/P3_7") (class "Default")
      (node (ref "IC6") (pin "30") (pinfunction "P0[30]/USB_D-_30") (pintype "bidirectional"))
      (node (ref "R71") (pin "2") (pinfunction "2_2") (pintype "passive"))
    )
    (net (code "73") (name "/P4_0") (class "Default")
      (node (ref "IC6") (pin "34") (pinfunction "P1[20]/MCI0/__PWM1[2]/SCK0_34") (pintype "bidirectional"))
      (node (ref "R72") (pin "2") (pinfunction "2_2") (pintype "passive"))
    )
    (net (code "74") (name "/P4_1") (class "Default")
      (node (ref "IC6") (pin "35") (pinfunction "P1[21]/~{MCABORT}/__PWM1[3]/__SSEL0_35") (pintype "bidirectional"))
      (node (ref "R73") (pin "2") (pinfunction "2_2") (pintype "passive"))
    )
    (net (code "75") (name "/P4_2") (class "Default")
      (node (ref "IC6") (pin "36") (pinfunction "P1[22]/MCOB0/__USB_PWRD/__MAT1[0]_36") (pintype "bidirectional"))
      (node (ref "R74") (pin "2") (pinfunction "2_2") (pintype "passive"))
    )
    (net (code "76") (name "/P4_3") (class "Default")
      (node (ref "IC6") (pin "37") (pinfunction "P1[23]/MCI1/__PWM1[4]/MISO0_37") (pintype "bidirectional"))
      (node (ref "R75") (pin "2") (pinfunction "2_2") (pintype "passive"))
    )
    (net (code "77") (name "/P4_4") (class "Default")
      (node (ref "IC6") (pin "38") (pinfunction "P1[24]/MCI2/__PWM1[5]/MOSI0_38") (pintype "bidirectional"))
      (node (ref "R76") (pin "2") (pinfunction "2_2") (pintype "passive"))
    )
    (net (code "78") (name "/P5_0") (class "Default")
      (node (ref "IC6") (pin "43") (pinfunction "P1[27]/CLKOUT__/~{USB_OVRCR}/__CAP0[1]_43") (pintype "bidirectional"))
      (node (ref "R77") (pin "2") (pinfunction "2_2") (pintype "passive"))
    )
    (net (code "79") (name "/P5_1") (class "Default")
      (node (ref "IC6") (pin "44") (pinfunction "P1[28]/MCOA2/__PCAP1[0]/__MAT0[0]_44") (pintype "bidirectional"))
      (node (ref "R79") (pin "2") (pinfunction "2_2") (pintype "passive"))
    )
    (net (code "80") (name "/P5_2") (class "Default")
      (node (ref "IC6") (pin "45") (pinfunction "P1[29]/MCOB2/__PCAP1[1]/__MAT0[1]_45") (pintype "bidirectional"))
      (node (ref "R81") (pin "2") (pinfunction "2_2") (pintype "passive"))
    )
    (net (code "81") (name "/P5_3") (class "Default")
      (node (ref "IC6") (pin "21") (pinfunction "P1[30]/VBUS/__AD0[4]_21") (pintype "bidirectional"))
      (node (ref "R83") (pin "2") (pinfunction "2_2") (pintype "passive"))
    )
    (net (code "82") (name "/P5_4") (class "Default")
      (node (ref "IC6") (pin "20") (pinfunction "P1[31]/SCK1/__AD0[5]_20") (pintype "bidirectional"))
      (node (ref "R87") (pin "2") (pinfunction "2_2") (pintype "passive"))
    )
    (net (code "83") (name "/PROG_RxD") (class "Default")
      (node (ref "CON17") (pin "9") (pinfunction "9_9") (pintype "passive"))
      (node (ref "IC6") (pin "99") (pinfunction "P0[3]/RXD0/AD0[6]_99") (pintype "bidirectional"))
    )
    (net (code "84") (name "/PROG_TxD") (class "Default")
      (node (ref "CON17") (pin "3") (pinfunction "3_3") (pintype "passive"))
      (node (ref "IC6") (pin "98") (pinfunction "P0[2]/TXD0/AD0[7]_98") (pintype "bidirectional"))
    )
    (net (code "85") (name "/RS0_A") (class "Default")
      (node (ref "R37") (pin "1") (pinfunction "1_1") (pintype "passive"))
    )
    (net (code "86") (name "/RS0_B") (class "Default")
      (node (ref "R46") (pin "1") (pinfunction "1_1") (pintype "passive"))
    )
    (net (code "87") (name "/RS0_C") (class "Default")
      (node (ref "R55") (pin "1") (pinfunction "1_1") (pintype "passive"))
    )
    (net (code "88") (name "/RS0_D") (class "Default")
      (node (ref "R66") (pin "1") (pinfunction "1_1") (pintype "passive"))
    )
    (net (code "89") (name "/RS1_A") (class "Default")
      (node (ref "R38") (pin "1") (pinfunction "1_1") (pintype "passive"))
    )
    (net (code "90") (name "/RS1_B") (class "Default")
      (node (ref "R47") (pin "1") (pinfunction "1_1") (pintype "passive"))
    )
    (net (code "91") (name "/RS1_C") (class "Default")
      (node (ref "R57") (pin "1") (pinfunction "1_1") (pintype "passive"))
    )
    (net (code "92") (name "/RS1_D") (class "Default")
      (node (ref "R67") (pin "1") (pinfunction "1_1") (pintype "passive"))
    )
    (net (code "93") (name "/RST") (class "Default")
      (node (ref "CON17") (pin "6") (pinfunction "6_6") (pintype "passive"))
      (node (ref "D1") (pin "1") (pinfunction "A_1") (pintype "passive"))
      (node (ref "IC6") (pin "17") (pinfunction "~{RESET}_17") (pintype "input"))
      (node (ref "JP9") (pin "6") (pinfunction "6_6") (pintype "passive"))
      (node (ref "R63") (pin "1") (pinfunction "1_1") (pintype "passive"))
      (node (ref "SW2") (pin "2") (pinfunction "2_2") (pintype "passive"))
    )
    (net (code "94") (name "/RSTO") (class "Default")
      (node (ref "IC6") (pin "14") (pinfunction "~{RSTOUT}_14") (pintype "output"))
    )
    (net (code "95") (name "/RST_A") (class "Default")
      (node (ref "R73") (pin "1") (pinfunction "1_1") (pintype "passive"))
    )
    (net (code "96") (name "/RST_B") (class "Default")
      (node (ref "R79") (pin "1") (pinfunction "1_1") (pintype "passive"))
    )
    (net (code "97") (name "/RXD0") (class "Default")
      (node (ref "IC6") (pin "91") (pinfunction "P1[9]/__ENET_RXD0_91") (pintype "bidirectional"))
    )
    (net (code "98") (name "/RXD1") (class "Default")
      (node (ref "IC6") (pin "90") (pinfunction "P1[10]/__ENET_RXD1_90") (pintype "bidirectional"))
    )
    (net (code "99") (name "/RXD_I") (class "Default")
      (node (ref "IC6") (pin "85") (pinfunction "P4[29]/TX_MCLK/__MAT2[1]/RXD3_85") (pintype "bidirectional"))
    )
    (net (code "100") (name "/RX_DV") (class "Default")
      (node (ref "IC6") (pin "92") (pinfunction "P1[8]/__ENET_CRS_92") (pintype "bidirectional"))
    )
    (net (code "101") (name "/RX_ER") (class "Default")
      (node (ref "IC6") (pin "89") (pinfunction "P1[14]/__ENET_RX_ER_89") (pintype "bidirectional"))
    )
    (net (code "102") (name "/SCL0") (class "Default")
      (node (ref "IC6") (pin "24") (pinfunction "P0[28]/SCL0/__USB_SCL_24") (pintype "bidirectional"))
      (node (ref "R85") (pin "1") (pinfunction "1_1") (pintype "passive"))
    )
    (net (code "103") (name "/SCL1") (class "Default")
      (node (ref "IC6") (pin "47") (pinfunction "P0[1]/TD1/RXD3/__SCL1_47") (pintype "bidirectional"))
      (node (ref "IC7") (pin "6") (pinfunction "SCL_6") (pintype "input"))
      (node (ref "R80") (pin "1") (pinfunction "1_1") (pintype "passive"))
    )
    (net (code "104") (name "/SCL2") (class "Default")
      (node (ref "IC6") (pin "49") (pinfunction "P0[11]/RXD2/__SCL2/MAT3[1]_49") (pintype "bidirectional"))
      (node (ref "R84") (pin "1") (pinfunction "1_1") (pintype "passive"))
    )
    (net (code "105") (name "/SDA0") (class "Default")
      (node (ref "IC6") (pin "25") (pinfunction "P0[27]/SDA0/__USB_SDA_25") (pintype "bidirectional"))
      (node (ref "R86") (pin "1") (pinfunction "1_1") (pintype "passive"))
    )
    (net (code "106") (name "/SDA1") (class "Default")
      (node (ref "IC6") (pin "46") (pinfunction "P0[0]/RD1/TXD3/__SDA1_46") (pintype "bidirectional"))
      (node (ref "IC7") (pin "5") (pinfunction "SDA_5") (pintype "bidirectional"))
      (node (ref "R78") (pin "1") (pinfunction "1_1") (pintype "passive"))
    )
    (net (code "107") (name "/SWCLK") (class "Default")
      (node (ref "CON17") (pin "1") (pinfunction "1_1") (pintype "passive"))
      (node (ref "IC6") (pin "5") (pinfunction "TCK/SWDCLK_5") (pintype "input"))
      (node (ref "JP9") (pin "1") (pinfunction "1_1") (pintype "passive"))
      (node (ref "R58") (pin "2") (pinfunction "2_2") (pintype "passive"))
    )
    (net (code "108") (name "/SWDIO") (class "Default")
      (node (ref "CON17") (pin "5") (pinfunction "5_5") (pintype "passive"))
      (node (ref "IC6") (pin "3") (pinfunction "TMS/SWDIO_3") (pintype "bidirectional"))
      (node (ref "JP9") (pin "5") (pinfunction "5_5") (pintype "passive"))
      (node (ref "R54") (pin "1") (pinfunction "1_1") (pintype "passive"))
    )
    (net (code "109") (name "/TDI") (class "Default")
      (node (ref "IC6") (pin "2") (pinfunction "TDI_2") (pintype "input"))
      (node (ref "JP9") (pin "9") (pinfunction "9_9") (pintype "passive"))
    )
    (net (code "110") (name "/TDO") (class "Default")
      (node (ref "IC6") (pin "1") (pinfunction "TDO/SWO_1") (pintype "output"))
      (node (ref "JP9") (pin "3") (pinfunction "3_3") (pintype "passive"))
    )
    (net (code "111") (name "/THERMn") (class "Default")
      (node (ref "IC6") (pin "32") (pinfunction "P1[18]/USB_UP_LED/PWM1[1]/_CAP1[0]_32") (pintype "bidirectional"))
    )
    (net (code "112") (name "/TRST") (class "Default")
      (node (ref "IC6") (pin "4") (pinfunction "~{TRST}_4") (pintype "input"))
      (node (ref "JP9") (pin "8") (pinfunction "8_8") (pintype "passive"))
      (node (ref "R56") (pin "1") (pinfunction "1_1") (pintype "passive"))
    )
    (net (code "113") (name "/TXD0") (class "Default")
      (node (ref "IC6") (pin "95") (pinfunction "P1[0]/__ENET_TXD0_95") (pintype "bidirectional"))
    )
    (net (code "114") (name "/TXD1") (class "Default")
      (node (ref "IC6") (pin "94") (pinfunction "P1[1]/__ENET_TXD1_94") (pintype "bidirectional"))
    )
    (net (code "115") (name "/TXDISABLE_A") (class "Default")
      (node (ref "R35") (pin "1") (pinfunction "1_1") (pintype "passive"))
    )
    (net (code "116") (name "/TXDISABLE_B") (class "Default")
      (node (ref "R44") (pin "1") (pinfunction "1_1") (pintype "passive"))
    )
    (net (code "117") (name "/TXDISABLE_C") (class "Default")
      (node (ref "R52") (pin "1") (pinfunction "1_1") (pintype "passive"))
    )
    (net (code "118") (name "/TXDISABLE_D") (class "Default")
      (node (ref "R64") (pin "1") (pinfunction "1_1") (pintype "passive"))
    )
    (net (code "119") (name "/TXD_O") (class "Default")
      (node (ref "IC6") (pin "82") (pinfunction "P4[28]/RX_MCLK/__MAT2[0]/TXD3_82") (pintype "bidirectional"))
    )
    (net (code "120") (name "/TXFAULT_A") (class "Default")
      (node (ref "R39") (pin "1") (pinfunction "1_1") (pintype "passive"))
    )
    (net (code "121") (name "/TXFAULT_B") (class "Default")
      (node (ref "R48") (pin "1") (pinfunction "1_1") (pintype "passive"))
    )
    (net (code "122") (name "/TXFAULT_C") (class "Default")
      (node (ref "R59") (pin "1") (pinfunction "1_1") (pintype "passive"))
    )
    (net (code "123") (name "/TXFAULT_D") (class "Default")
      (node (ref "R68") (pin "1") (pinfunction "1_1") (pintype "passive"))
    )
    (net (code "124") (name "/TX_CLK") (class "Default")
      (node (ref "IC6") (pin "88") (pinfunction "P1[15]/__ENET_REF_CLK_88") (pintype "bidirectional"))
    )
    (net (code "125") (name "/TX_EN") (class "Default")
      (node (ref "IC6") (pin "93") (pinfunction "P1[4]/__ENET_TX_EN_93") (pintype "bidirectional"))
    )
    (net (code "132") (name "GND") (class "Default")
      (node (ref "C25") (pin "1") (pinfunction "1_1") (pintype "passive"))
      (node (ref "C26") (pin "1") (pinfunction "1_1") (pintype "passive"))
      (node (ref "C27") (pin "1") (pinfunction "1_1") (pintype "passive"))
      (node (ref "C28") (pin "1") (pinfunction "1_1") (pintype "passive"))
      (node (ref "C29") (pin "1") (pinfunction "1_1") (pintype "passive"))
      (node (ref "C30") (pin "1") (pinfunction "1_1") (pintype "passive"))
      (node (ref "C31") (pin "1") (pinfunction "1_1") (pintype "passive"))
      (node (ref "C32") (pin "1") (pinfunction "1_1") (pintype "passive"))
      (node (ref "C33") (pin "1") (pinfunction "1_1") (pintype "passive"))
      (node (ref "C34") (pin "1") (pinfunction "1_1") (pintype "passive"))
      (node (ref "C35") (pin "1") (pinfunction "1_1") (pintype "passive"))
      (node (ref "C36") (pin "1") (pinfunction "1_1") (pintype "passive"))
      (node (ref "CON17") (pin "10") (pinfunction "10_10") (pintype "passive"))
      (node (ref "CON17") (pin "2") (pinfunction "2_2") (pintype "passive"))
      (node (ref "IC6") (pin "11") (pinfunction "VSSA_11") (pintype "power_in"))
      (node (ref "IC6") (pin "15") (pinfunction "VREFN_15") (pintype "power_in"))
      (node (ref "IC6") (pin "31") (pinfunction "VSS_31") (pintype "power_in"))
      (node (ref "IC6") (pin "41") (pinfunction "VSS_41") (pintype "power_in"))
      (node (ref "IC6") (pin "55") (pinfunction "VSS_55") (pintype "power_in"))
      (node (ref "IC6") (pin "72") (pinfunction "VSS_72") (pintype "power_in"))
      (node (ref "IC6") (pin "83") (pinfunction "VSS_83") (pintype "power_in"))
      (node (ref "IC6") (pin "97") (pinfunction "VSS_97") (pintype "power_in"))
      (node (ref "IC7") (pin "1") (pinfunction "A0_1") (pintype "input"))
      (node (ref "IC7") (pin "2") (pinfunction "A1_2") (pintype "input"))
      (node (ref "IC7") (pin "3") (pinfunction "A2_3") (pintype "input"))
      (node (ref "IC7") (pin "4") (pinfunction "GND_4") (pintype "power_in"))
      (node (ref "IC7") (pin "7") (pinfunction "WP_7") (pintype "passive"))
      (node (ref "IC8") (pin "1") (pinfunction "Vss_1") (pintype "power_in"))
      (node (ref "JP9") (pin "10") (pinfunction "10_10") (pintype "passive"))
      (node (ref "JP9") (pin "2") (pinfunction "2_2") (pintype "passive"))
      (node (ref "R58") (pin "1") (pinfunction "1_1") (pintype "passive"))
      (node (ref "SW2") (pin "1") (pinfunction "1_1") (pintype "passive"))
    )
    (net (code "133") (name "Net-(D1-C)") (class "Default")
      (node (ref "D1") (pin "3") (pinfunction "C_3") (pintype "passive"))
      (node (ref "IC8") (pin "2") (pinfunction "~{RST}_2") (pintype "output"))
    )
    (net (code "134") (name "Net-(IC6A-RTCX1)") (class "Default")
      (node (ref "IC6") (pin "16") (pinfunction "RTCX1_16") (pintype "input"))
      (node (ref "TP1") (pin "1") (pintype "passive"))
    )
    (net (code "135") (name "Net-(IC6A-RTCX2)") (class "Default")
      (node (ref "IC6") (pin "18") (pinfunction "RTCX2_18") (pintype "output"))
      (node (ref "TP2") (pin "1") (pintype "passive"))
    )
    (net (code "136") (name "Net-(IC6A-VDDA)") (class "Default")
      (node (ref "C27") (pin "2") (pinfunction "2_2") (pintype "passive"))
      (node (ref "FB1") (pin "1") (pinfunction "1_1") (pintype "passive"))
      (node (ref "IC6") (pin "10") (pinfunction "VDDA_10") (pintype "power_in"))
      (node (ref "IC6") (pin "12") (pinfunction "VREFP_12") (pintype "power_in"))
    )
    (net (code "137") (name "Net-(IC6A-XTAL1)") (class "Default")
      (node (ref "C25") (pin "2") (pinfunction "2_2") (pintype "passive"))
      (node (ref "IC6") (pin "22") (pinfunction "XTAL1_22") (pintype "input"))
      (node (ref "X1") (pin "1") (pinfunction "1_1") (pintype "passive"))
    )
    (net (code "138") (name "Net-(IC6A-XTAL2)") (class "Default")
      (node (ref "C26") (pin "2") (pinfunction "2_2") (pintype "passive"))
      (node (ref "IC6") (pin "23") (pinfunction "XTAL2_23") (pintype "output"))
      (node (ref "X1") (pin "2") (pinfunction "2_2") (pintype "passive"))
    )
    (net (code "139") (name "P3V3") (class "Default")
      (node (ref "C28") (pin "2") (pinfunction "2_2") (pintype "passive"))
      (node (ref "C29") (pin "2") (pinfunction "2_2") (pintype "passive"))
      (node (ref "C30") (pin "2") (pinfunction "2_2") (pintype "passive"))
      (node (ref "C31") (pin "2") (pinfunction "2_2") (pintype "passive"))
      (node (ref "C32") (pin "2") (pinfunction "2_2") (pintype "passive"))
      (node (ref "C33") (pin "2") (pinfunction "2_2") (pintype "passive"))
      (node (ref "C34") (pin "2") (pinfunction "2_2") (pintype "passive"))
      (node (ref "C35") (pin "2") (pinfunction "2_2") (pintype "passive"))
      (node (ref "C36") (pin "2") (pinfunction "2_2") (pintype "passive"))
      (node (ref "CON17") (pin "4") (pinfunction "4_4") (pintype "passive"))
      (node (ref "FB1") (pin "2") (pinfunction "2_2") (pintype "passive"))
      (node (ref "IC6") (pin "19") (pinfunction "VBAT_19") (pintype "power_in"))
      (node (ref "IC6") (pin "28") (pinfunction "VDD(3V3)_28") (pintype "power_in"))
      (node (ref "IC6") (pin "42") (pinfunction "VDD(REG)(3V3)_42") (pintype "power_in"))
      (node (ref "IC6") (pin "54") (pinfunction "VDD(3V3)_54") (pintype "power_in"))
      (node (ref "IC6") (pin "71") (pinfunction "VDD(3V3)_71") (pintype "power_in"))
      (node (ref "IC6") (pin "84") (pinfunction "VDD(REG)(3V3)_84") (pintype "power_in"))
      (node (ref "IC6") (pin "96") (pinfunction "VDD(3V3)_96") (pintype "power_in"))
      (node (ref "IC7") (pin "8") (pinfunction "VCC_8") (pintype "power_in"))
      (node (ref "IC8") (pin "3") (pinfunction "Vcc_3") (pintype "power_in"))
      (node (ref "JP9") (pin "4") (pinfunction "4_4") (pintype "passive"))
      (node (ref "R43") (pin "2") (pinfunction "2_2") (pintype "passive"))
      (node (ref "R54") (pin "2") (pinfunction "2_2") (pintype "passive"))
      (node (ref "R56") (pin "2") (pinfunction "2_2") (pintype "passive"))
      (node (ref "R63") (pin "2") (pinfunction "2_2") (pintype "passive"))
      (node (ref "R78") (pin "2") (pinfunction "2_2") (pintype "passive"))
      (node (ref "R80") (pin "2") (pinfunction "2_2") (pintype "passive"))
      (node (ref "R82") (pin "2") (pinfunction "2_2") (pintype "passive"))
      (node (ref "R84") (pin "2") (pinfunction "2_2") (pintype "passive"))
      (node (ref "R85") (pin "2") (pinfunction "2_2") (pintype "passive"))
      (node (ref "R86") (pin "2") (pinfunction "2_2") (pintype "passive"))
    )
    (net (code "140") (name "unconnected-(CON17-Pad7)") (class "Default")
      (node (ref "CON17") (pin "7") (pinfunction "7_7") (pintype "passive"))
    )
    (net (code "141") (name "unconnected-(IC6A-N.C.-Pad13)") (class "Default")
      (node (ref "IC6") (pin "13") (pinfunction "N.C._13") (pintype "tri_state"))
    )
    (net (code "142") (name "unconnected-(IC6A-RTCK-Pad100)") (class "Default")
      (node (ref "IC6") (pin "100") (pinfunction "RTCK_100") (pintype "output"))
    )
    (net (code "143") (name "unconnected-(JP9-Pad7)") (class "Default")
      (node (ref "JP9") (pin "7") (pinfunction "7_7") (pintype "passive"))
    )
  )
)
